# Adafruit_Feather_M0_Adalogger.net
KiCad netlist of a schematic drawn in EAGLE
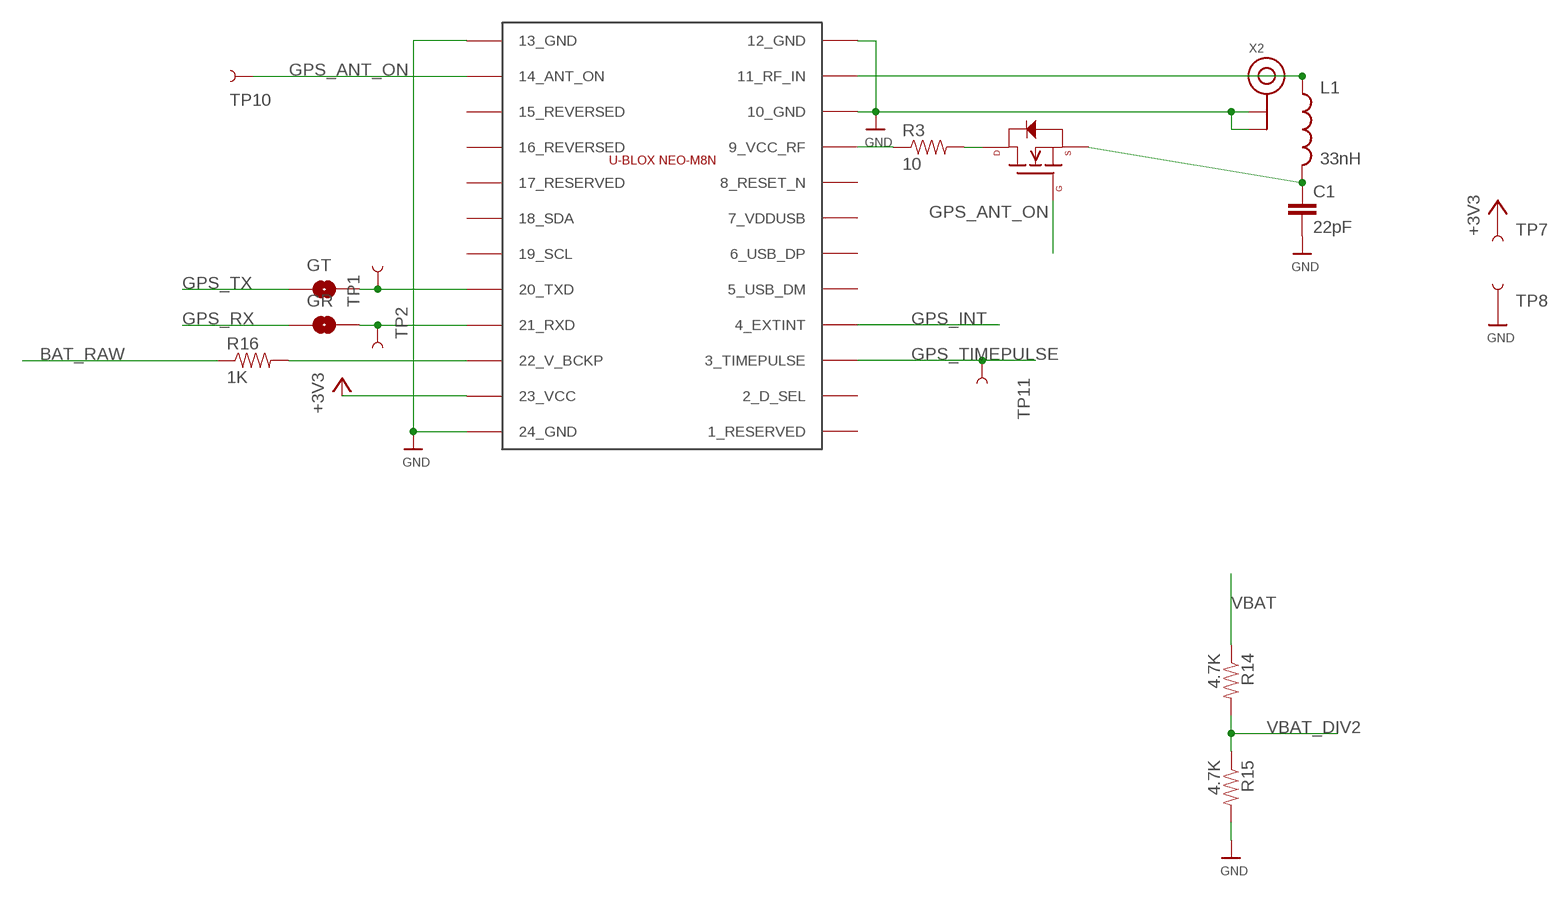
[diagram p0: schematic, sheet 1, part 1 of 2]
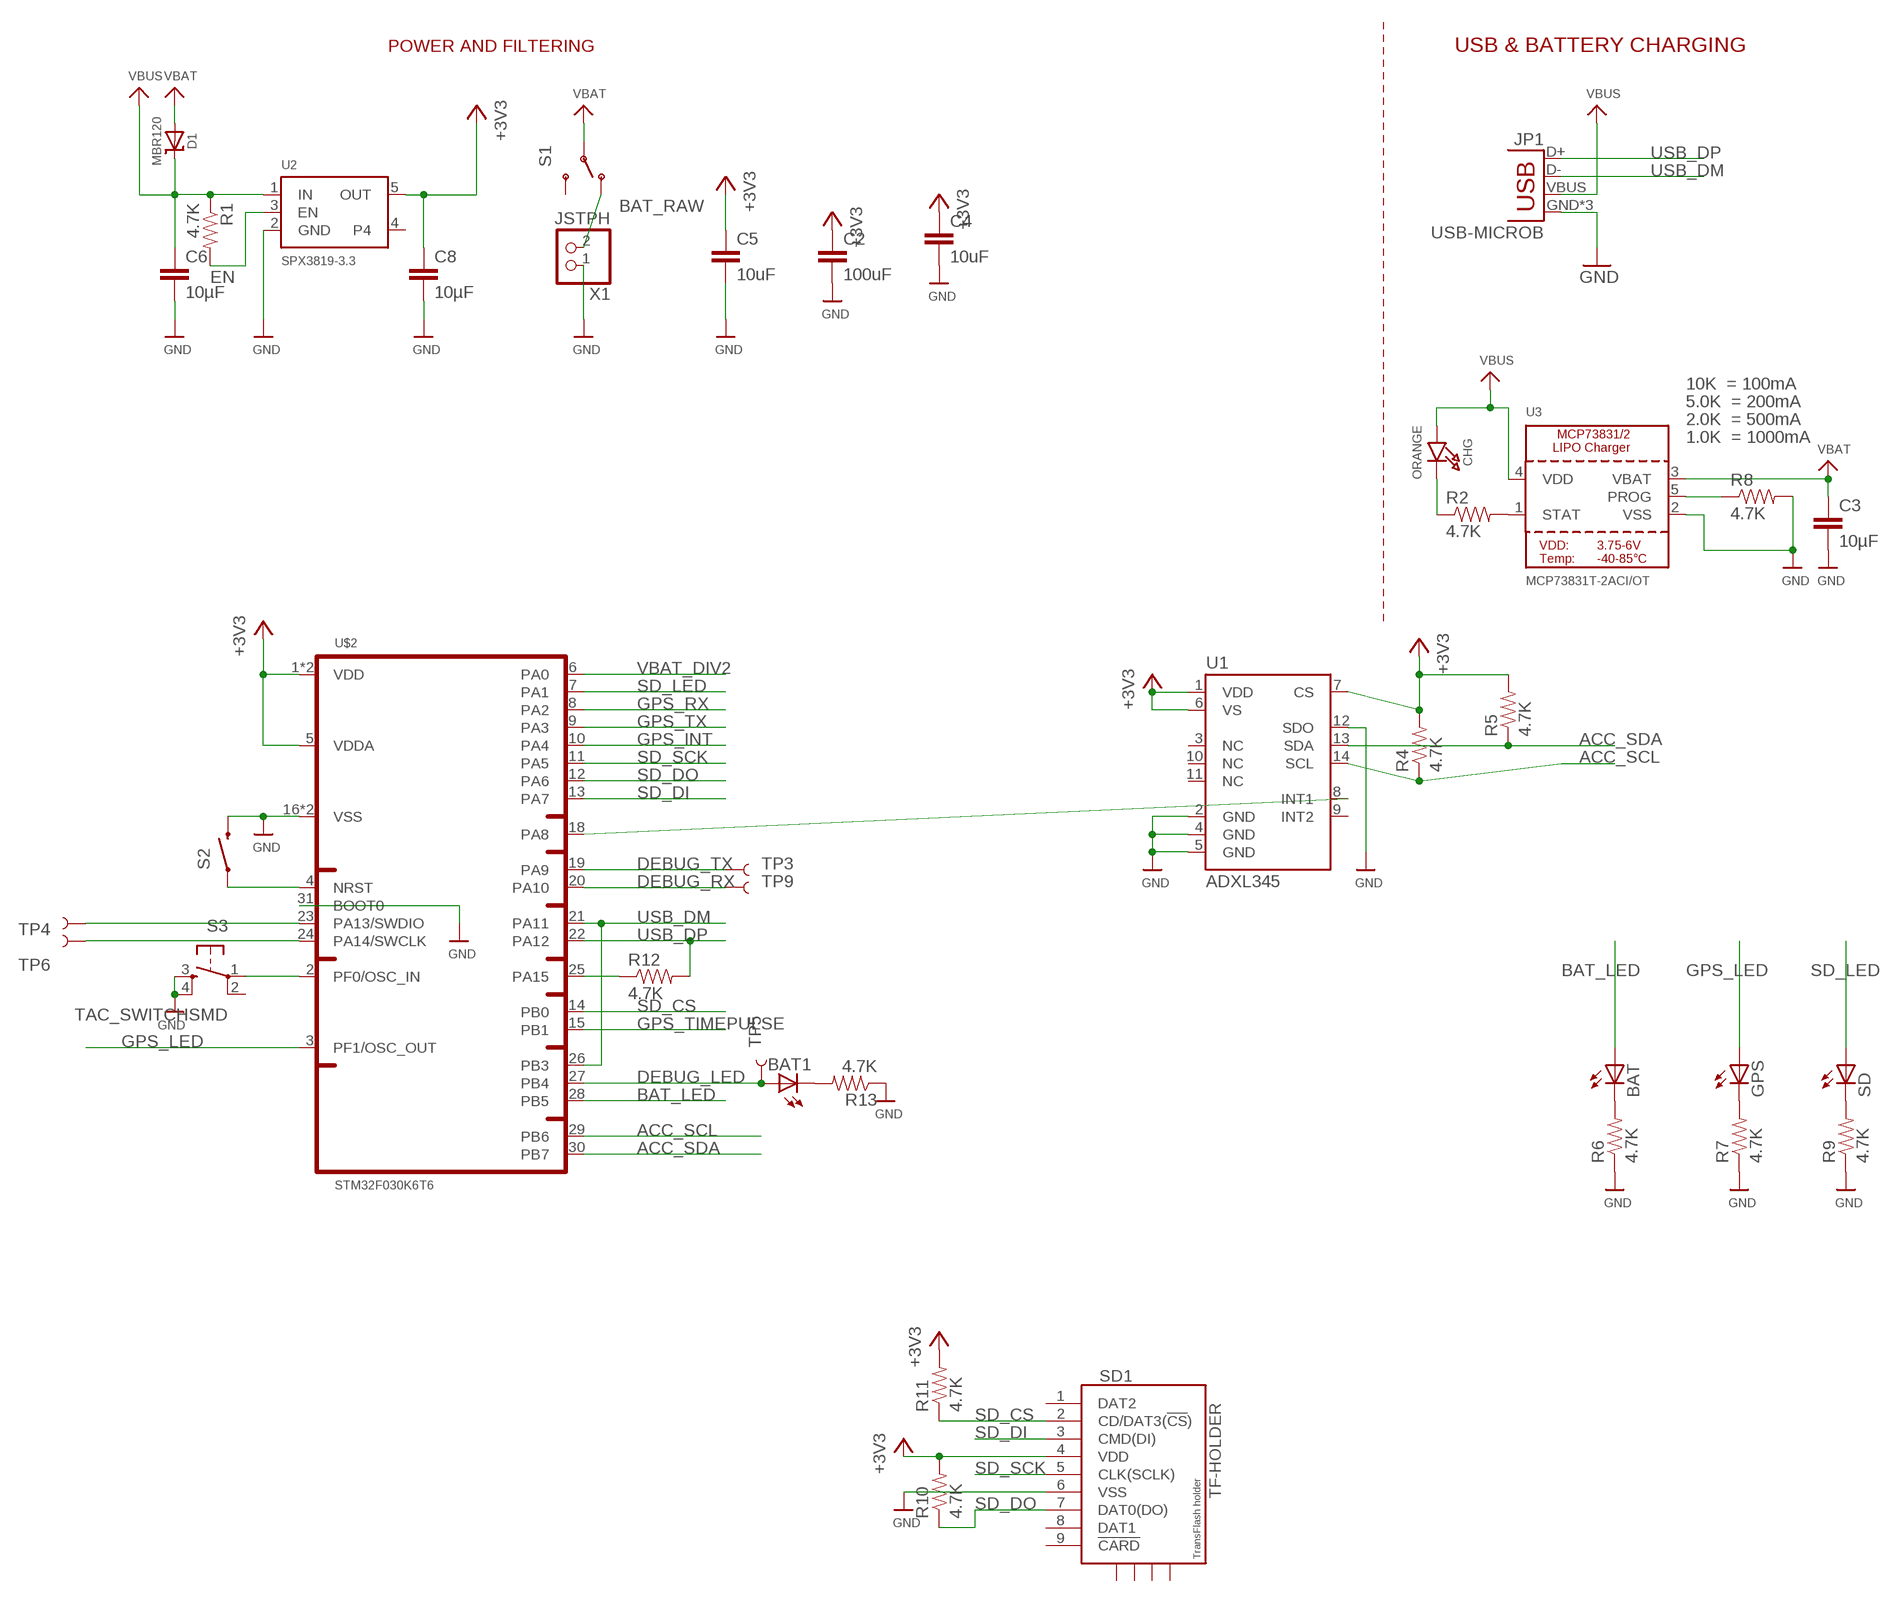
[diagram p1: schematic, sheet 1, part 2 of 2]

(export (version "E")
  (design (tool "Eeschema 10.0.6"))
  (components
    (comp (ref "BAT")
      (value "LEDCHIPLED_0805")
      (footprint "eagle-import:CHIPLED_0805")
      (libsource (lib "eagle-import") (part "LEDCHIPLED_0805"))
    )
    (comp (ref "BAT1")
      (value "LEDCHIPLED_0805")
      (footprint "eagle-import:CHIPLED_0805")
      (libsource (lib "eagle-import") (part "LEDCHIPLED_0805"))
    )
    (comp (ref "C1")
      (value "22pF")
      (footprint "eagle-import:0805")
      (libsource (lib "eagle-import") (part "CAP0805"))
    )
    (comp (ref "C2")
      (value "100uF")
      (footprint "eagle-import:1210")
      (libsource (lib "eagle-import") (part "100UF6.3V20%(1210)"))
    )
    (comp (ref "C3")
      (value "10µF")
      (footprint "eagle-import:0805")
      (libsource (lib "eagle-import") (part "CAP0805"))
    )
    (comp (ref "C4")
      (value "10uF")
      (footprint "eagle-import:0805")
      (libsource (lib "eagle-import") (part "CAP0805"))
    )
    (comp (ref "C5")
      (value "10uF")
      (footprint "eagle-import:0805")
      (libsource (lib "eagle-import") (part "CAP0805"))
    )
    (comp (ref "C6")
      (value "10µF")
      (footprint "eagle-import:0805")
      (libsource (lib "eagle-import") (part "CAP0805"))
    )
    (comp (ref "C8")
      (value "10µF")
      (footprint "eagle-import:0805")
      (libsource (lib "eagle-import") (part "CAP0805"))
    )
    (comp (ref "CHG")
      (value "ORANGE")
      (footprint "eagle-import:CHIPLED_0805_NOOUTLINE")
      (libsource (lib "eagle-import") (part "LED0805_NOOUTLINE"))
    )
    (comp (ref "D1")
      (value "MBR120")
      (footprint "eagle-import:SOD-123")
      (libsource (lib "eagle-import") (part "DIODE-SCHOTTKYSOD-123"))
    )
    (comp (ref "DEKU1")
      (value "UBLOX_NEO-M8N")
      (footprint "eagle-import:UBLOX_NEO-M8N")
      (libsource (lib "eagle-import") (part "UBLOX_NEO-M8N"))
    )
    (comp (ref "GPS")
      (value "LEDCHIPLED_0805")
      (footprint "eagle-import:CHIPLED_0805")
      (libsource (lib "eagle-import") (part "LEDCHIPLED_0805"))
    )
    (comp (ref "GR")
      (value "JUMPER-PAD-2-NO")
      (footprint "eagle-import:PAD-JUMPER-2-NO_NO_SILK")
      (libsource (lib "eagle-import") (part "JUMPER-PAD-2-NO"))
    )
    (comp (ref "GT")
      (value "JUMPER-PAD-2-NO")
      (footprint "eagle-import:PAD-JUMPER-2-NO_NO_SILK")
      (libsource (lib "eagle-import") (part "JUMPER-PAD-2-NO"))
    )
    (comp (ref "JP1")
      (value "USB-MICROB")
      (footprint "eagle-import:USB-MICROB")
      (libsource (lib "eagle-import") (part "USB-MICROB"))
    )
    (comp (ref "L1")
      (value "33nH")
      (footprint "eagle-import:0805")
      (libsource (lib "eagle-import") (part "INDUCTOR0805"))
    )
    (comp (ref "R1")
      (value "4.7K")
      (footprint "eagle-import:0805")
      (libsource (lib "eagle-import") (part "RESISTOR0805-RES"))
    )
    (comp (ref "R2")
      (value "4.7K")
      (footprint "eagle-import:0805")
      (libsource (lib "eagle-import") (part "RESISTOR0805-RES"))
    )
    (comp (ref "R3")
      (value "10")
      (footprint "eagle-import:0805")
      (libsource (lib "eagle-import") (part "RESISTOR0805-RES"))
    )
    (comp (ref "R4")
      (value "4.7K")
      (footprint "eagle-import:0805")
      (libsource (lib "eagle-import") (part "RESISTOR0805-RES"))
    )
    (comp (ref "R5")
      (value "4.7K")
      (footprint "eagle-import:0805")
      (libsource (lib "eagle-import") (part "RESISTOR0805-RES"))
    )
    (comp (ref "R6")
      (value "4.7K")
      (footprint "eagle-import:0805")
      (libsource (lib "eagle-import") (part "RESISTOR0805-RES"))
    )
    (comp (ref "R7")
      (value "4.7K")
      (footprint "eagle-import:0805")
      (libsource (lib "eagle-import") (part "RESISTOR0805-RES"))
    )
    (comp (ref "R8")
      (value "4.7K")
      (footprint "eagle-import:0805")
      (libsource (lib "eagle-import") (part "RESISTOR0805-RES"))
    )
    (comp (ref "R9")
      (value "4.7K")
      (footprint "eagle-import:0805")
      (libsource (lib "eagle-import") (part "RESISTOR0805-RES"))
    )
    (comp (ref "R10")
      (value "4.7K")
      (footprint "eagle-import:0805")
      (libsource (lib "eagle-import") (part "RESISTOR0805-RES"))
    )
    (comp (ref "R11")
      (value "4.7K")
      (footprint "eagle-import:0805")
      (libsource (lib "eagle-import") (part "RESISTOR0805-RES"))
    )
    (comp (ref "R12")
      (value "4.7K")
      (footprint "eagle-import:0805")
      (libsource (lib "eagle-import") (part "RESISTOR0805-RES"))
    )
    (comp (ref "R13")
      (value "4.7K")
      (footprint "eagle-import:0805")
      (libsource (lib "eagle-import") (part "RESISTOR0805-RES"))
    )
    (comp (ref "R14")
      (value "4.7K")
      (footprint "eagle-import:0805")
      (libsource (lib "eagle-import") (part "RESISTOR0805-RES"))
    )
    (comp (ref "R15")
      (value "4.7K")
      (footprint "eagle-import:0805")
      (libsource (lib "eagle-import") (part "RESISTOR0805-RES"))
    )
    (comp (ref "R16")
      (value "1K")
      (footprint "eagle-import:0805")
      (libsource (lib "eagle-import") (part "RESISTOR0805-RES"))
    )
    (comp (ref "S1")
      (value "SWITCH-SPDT-SMD-A")
      (footprint "eagle-import:SWITCH-SPST-SMD-A")
      (libsource (lib "eagle-import") (part "SWITCH-SPDT-SMD-A"))
    )
    (comp (ref "S2")
      (value "SWITCH-MOMENTARY-2TURTLE")
      (footprint "eagle-import:KMR2")
      (libsource (lib "eagle-import") (part "SWITCH-MOMENTARY-2TURTLE"))
    )
    (comp (ref "S3")
      (value "TAC_SWITCHSMD")
      (footprint "eagle-import:TACTILE-SWITCH-SMD")
      (libsource (lib "eagle-import") (part "TAC_SWITCHSMD"))
    )
    (comp (ref "SD")
      (value "LEDCHIPLED_0805")
      (footprint "eagle-import:CHIPLED_0805")
      (libsource (lib "eagle-import") (part "LEDCHIPLED_0805"))
    )
    (comp (ref "SD1")
      (value "TF-HOLDER")
      (footprint "eagle-import:TF-PULL")
      (libsource (lib "eagle-import") (part "TF-HOLDER"))
    )
    (comp (ref "TP1")
      (value "TEST-POINT3X5")
      (footprint "eagle-import:PAD.03X.05")
      (libsource (lib "eagle-import") (part "TEST-POINT3X5"))
    )
    (comp (ref "TP2")
      (value "TEST-POINT3X5")
      (footprint "eagle-import:PAD.03X.05")
      (libsource (lib "eagle-import") (part "TEST-POINT3X5"))
    )
    (comp (ref "TP3")
      (value "TEST-POINT3X5")
      (footprint "eagle-import:PAD.03X.05")
      (libsource (lib "eagle-import") (part "TEST-POINT3X5"))
    )
    (comp (ref "TP4")
      (value "TEST-POINT3X5")
      (footprint "eagle-import:PAD.03X.05")
      (libsource (lib "eagle-import") (part "TEST-POINT3X5"))
    )
    (comp (ref "TP5")
      (value "TEST-POINT3X5")
      (footprint "eagle-import:PAD.03X.05")
      (libsource (lib "eagle-import") (part "TEST-POINT3X5"))
    )
    (comp (ref "TP6")
      (value "TEST-POINT3X5")
      (footprint "eagle-import:PAD.03X.05")
      (libsource (lib "eagle-import") (part "TEST-POINT3X5"))
    )
    (comp (ref "TP7")
      (value "TEST-POINT3X5")
      (footprint "eagle-import:PAD.03X.05")
      (libsource (lib "eagle-import") (part "TEST-POINT3X5"))
    )
    (comp (ref "TP8")
      (value "TEST-POINT3X5")
      (footprint "eagle-import:PAD.03X.05")
      (libsource (lib "eagle-import") (part "TEST-POINT3X5"))
    )
    (comp (ref "TP9")
      (value "TEST-POINT3X5")
      (footprint "eagle-import:PAD.03X.05")
      (libsource (lib "eagle-import") (part "TEST-POINT3X5"))
    )
    (comp (ref "TP10")
      (value "TEST-POINT3X5")
      (footprint "eagle-import:PAD.03X.05")
      (libsource (lib "eagle-import") (part "TEST-POINT3X5"))
    )
    (comp (ref "TP11")
      (value "TEST-POINT3X5")
      (footprint "eagle-import:PAD.03X.05")
      (libsource (lib "eagle-import") (part "TEST-POINT3X5"))
    )
    (comp (ref "U$2")
      (value "STM32F030K6T6")
      (footprint "eagle-import:TQFP32-08")
      (libsource (lib "eagle-import") (part "STM32F030K6T6"))
    )
    (comp (ref "U$24")
      (value "N-CHANNEL-MOSFET-BSS138")
      (footprint "eagle-import:SOT23-3")
      (libsource (lib "eagle-import") (part "N-CHANNEL-MOSFET-BSS138"))
    )
    (comp (ref "U1")
      (value "ADXL345")
      (footprint "eagle-import:LGA14")
      (libsource (lib "eagle-import") (part "ADXL345"))
    )
    (comp (ref "U2")
      (value "SPX3819-3.3")
      (footprint "eagle-import:SOT23-5")
      (libsource (lib "eagle-import") (part "VREG_SOT23-5"))
    )
    (comp (ref "U3")
      (value "MCP73831T-2ACI/OT")
      (footprint "eagle-import:SOT23-5")
      (libsource (lib "eagle-import") (part "MCP73831/2"))
    )
    (comp (ref "X1")
      (value "JSTPH")
      (footprint "eagle-import:JSTPH2")
      (libsource (lib "eagle-import") (part "CON_JST_PH_2PIN"))
    )
    (comp (ref "X2")
      (value "ANTENNA_U.FL")
      (footprint "eagle-import:U.FL")
      (libsource (lib "eagle-import") (part "ANTENNA_U.FL"))
    )
  )
  (nets
    (net (code "1") (name "+3V3") (class "Default")
      (node (ref "C2") (pin "1") (pinfunction "1_1") (pintype "passive"))
      (node (ref "C4") (pin "1") (pinfunction "1_1") (pintype "passive"))
      (node (ref "C5") (pin "1") (pinfunction "1_1") (pintype "passive"))
      (node (ref "C8") (pin "1") (pinfunction "1_1") (pintype "passive"))
      (node (ref "DEKU1") (pin "23_VCC") (pinfunction "23_VCC_23_VCC") (pintype "bidirectional"))
      (node (ref "R10") (pin "2") (pinfunction "2_2") (pintype "passive"))
      (node (ref "R11") (pin "2") (pinfunction "2_2") (pintype "passive"))
      (node (ref "R4") (pin "2") (pinfunction "2_2") (pintype "passive"))
      (node (ref "R5") (pin "2") (pinfunction "2_2") (pintype "passive"))
      (node (ref "SD1") (pin "4") (pinfunction "VDD_4") (pintype "power_in"))
      (node (ref "TP7") (pin "P$1") (pinfunction "1_P$1") (pintype "bidirectional"))
      (node (ref "U$2") (pin "1") (pinfunction "VDD_1") (pintype "bidirectional"))
      (node (ref "U$2") (pin "17") (pinfunction "VDD_17") (pintype "bidirectional"))
      (node (ref "U$2") (pin "5") (pinfunction "VDDA_5") (pintype "bidirectional"))
      (node (ref "U1") (pin "1") (pinfunction "VDD_1") (pintype "bidirectional"))
      (node (ref "U1") (pin "6") (pinfunction "VS_6") (pintype "bidirectional"))
      (node (ref "U1") (pin "7") (pinfunction "CS_7") (pintype "bidirectional"))
      (node (ref "U2") (pin "5") (pinfunction "OUT_5") (pintype "power_in"))
    )
    (net (code "2") (name "/ACC_SCL") (class "Default")
      (node (ref "R4") (pin "1") (pinfunction "1_1") (pintype "passive"))
      (node (ref "U$2") (pin "29") (pinfunction "PB6_29") (pintype "bidirectional"))
      (node (ref "U1") (pin "14") (pinfunction "SCL_14") (pintype "bidirectional"))
    )
    (net (code "3") (name "/ACC_SDA") (class "Default")
      (node (ref "R5") (pin "1") (pinfunction "1_1") (pintype "passive"))
      (node (ref "U$2") (pin "30") (pinfunction "PB7_30") (pintype "bidirectional"))
      (node (ref "U1") (pin "13") (pinfunction "SDA_13") (pintype "bidirectional"))
    )
    (net (code "4") (name "/BAT_LED") (class "Default")
      (node (ref "BAT") (pin "A") (pinfunction "A_A") (pintype "passive"))
      (node (ref "U$2") (pin "28") (pinfunction "PB5_28") (pintype "bidirectional"))
    )
    (net (code "5") (name "/BAT_RAW") (class "Default")
      (node (ref "R16") (pin "1") (pinfunction "1_1") (pintype "passive"))
      (node (ref "S1") (pin "1") (pinfunction "O_1") (pintype "passive"))
      (node (ref "X1") (pin "2") (pinfunction "2_2") (pintype "passive"))
    )
    (net (code "6") (name "/DEBUG_LED") (class "Default")
      (node (ref "BAT1") (pin "A") (pinfunction "A_A") (pintype "passive"))
      (node (ref "TP5") (pin "P$1") (pinfunction "1_P$1") (pintype "bidirectional"))
      (node (ref "U$2") (pin "27") (pinfunction "PB4_27") (pintype "bidirectional"))
    )
    (net (code "7") (name "/DEBUG_RX") (class "Default")
      (node (ref "TP9") (pin "P$1") (pinfunction "1_P$1") (pintype "bidirectional"))
      (node (ref "U$2") (pin "20") (pinfunction "PA10_20") (pintype "bidirectional"))
    )
    (net (code "8") (name "/DEBUG_TX") (class "Default")
      (node (ref "TP3") (pin "P$1") (pinfunction "1_P$1") (pintype "bidirectional"))
      (node (ref "U$2") (pin "19") (pinfunction "PA9_19") (pintype "bidirectional"))
    )
    (net (code "9") (name "/EN") (class "Default")
      (node (ref "R1") (pin "2") (pinfunction "2_2") (pintype "passive"))
      (node (ref "U2") (pin "3") (pinfunction "EN_3") (pintype "input"))
    )
    (net (code "10") (name "/GPS_ANT_ON") (class "Default")
      (node (ref "DEKU1") (pin "14_ANT_ON") (pinfunction "14_ANT_ON_14_ANT_ON") (pintype "bidirectional"))
      (node (ref "TP10") (pin "P$1") (pinfunction "1_P$1") (pintype "bidirectional"))
      (node (ref "U$24") (pin "1") (pinfunction "G_1") (pintype "passive"))
    )
    (net (code "11") (name "/GPS_INT") (class "Default")
      (node (ref "DEKU1") (pin "4_EXTINT") (pinfunction "4_EXTINT_4_EXTINT") (pintype "bidirectional"))
      (node (ref "U$2") (pin "10") (pinfunction "PA4_10") (pintype "bidirectional"))
    )
    (net (code "12") (name "/GPS_LED") (class "Default")
      (node (ref "GPS") (pin "A") (pinfunction "A_A") (pintype "passive"))
      (node (ref "U$2") (pin "3") (pinfunction "PF1/OSC_OUT_3") (pintype "bidirectional"))
    )
    (net (code "13") (name "/GPS_RX") (class "Default")
      (node (ref "GR") (pin "1") (pinfunction "1_1") (pintype "passive"))
      (node (ref "U$2") (pin "8") (pinfunction "PA2_8") (pintype "bidirectional"))
    )
    (net (code "14") (name "/GPS_TIMEPULSE") (class "Default")
      (node (ref "DEKU1") (pin "3_TIMEPULSE") (pinfunction "3_TIMEPULSE_3_TIMEPULSE") (pintype "bidirectional"))
      (node (ref "TP11") (pin "P$1") (pinfunction "1_P$1") (pintype "bidirectional"))
      (node (ref "U$2") (pin "15") (pinfunction "PB1_15") (pintype "bidirectional"))
    )
    (net (code "15") (name "/GPS_TX") (class "Default")
      (node (ref "GT") (pin "1") (pinfunction "1_1") (pintype "passive"))
      (node (ref "U$2") (pin "9") (pinfunction "PA3_9") (pintype "bidirectional"))
    )
    (net (code "16") (name "/SD_CS") (class "Default")
      (node (ref "R11") (pin "1") (pinfunction "1_1") (pintype "passive"))
      (node (ref "SD1") (pin "2") (pinfunction "CD/DAT3(~{CS})_2") (pintype "bidirectional"))
      (node (ref "U$2") (pin "14") (pinfunction "PB0_14") (pintype "bidirectional"))
    )
    (net (code "17") (name "/SD_DI") (class "Default")
      (node (ref "SD1") (pin "3") (pinfunction "CMD(DI)_3") (pintype "bidirectional"))
      (node (ref "U$2") (pin "13") (pinfunction "PA7_13") (pintype "bidirectional"))
    )
    (net (code "18") (name "/SD_DO") (class "Default")
      (node (ref "R10") (pin "1") (pinfunction "1_1") (pintype "passive"))
      (node (ref "SD1") (pin "7") (pinfunction "DAT0(DO)_7") (pintype "bidirectional"))
      (node (ref "U$2") (pin "12") (pinfunction "PA6_12") (pintype "bidirectional"))
    )
    (net (code "19") (name "/SD_LED") (class "Default")
      (node (ref "SD") (pin "A") (pinfunction "A_A") (pintype "passive"))
      (node (ref "U$2") (pin "7") (pinfunction "PA1_7") (pintype "bidirectional"))
    )
    (net (code "20") (name "/SD_SCK") (class "Default")
      (node (ref "SD1") (pin "5") (pinfunction "CLK(SCLK)_5") (pintype "input"))
      (node (ref "U$2") (pin "11") (pinfunction "PA5_11") (pintype "bidirectional"))
    )
    (net (code "21") (name "/USB_DM") (class "Default")
      (node (ref "JP1") (pin "D-") (pinfunction "D-_D-") (pintype "bidirectional"))
      (node (ref "U$2") (pin "21") (pinfunction "PA11_21") (pintype "bidirectional"))
      (node (ref "U$2") (pin "26") (pinfunction "PB3_26") (pintype "bidirectional"))
    )
    (net (code "22") (name "/USB_DP") (class "Default")
      (node (ref "JP1") (pin "D+") (pinfunction "D+_D+") (pintype "bidirectional"))
      (node (ref "R12") (pin "2") (pinfunction "2_2") (pintype "passive"))
      (node (ref "U$2") (pin "22") (pinfunction "PA12_22") (pintype "bidirectional"))
    )
    (net (code "23") (name "/VBAT_DIV2") (class "Default")
      (node (ref "R14") (pin "2") (pinfunction "2_2") (pintype "passive"))
      (node (ref "R15") (pin "1") (pinfunction "1_1") (pintype "passive"))
      (node (ref "U$2") (pin "6") (pinfunction "PA0_6") (pintype "bidirectional"))
    )
    (net (code "24") (name "GND") (class "Default")
      (node (ref "C1") (pin "2") (pinfunction "2_2") (pintype "passive"))
      (node (ref "C2") (pin "2") (pinfunction "2_2") (pintype "passive"))
      (node (ref "C3") (pin "2") (pinfunction "2_2") (pintype "passive"))
      (node (ref "C4") (pin "2") (pinfunction "2_2") (pintype "passive"))
      (node (ref "C5") (pin "2") (pinfunction "2_2") (pintype "passive"))
      (node (ref "C6") (pin "2") (pinfunction "2_2") (pintype "passive"))
      (node (ref "C8") (pin "2") (pinfunction "2_2") (pintype "passive"))
      (node (ref "DEKU1") (pin "10_GND") (pinfunction "10_GND_10_GND") (pintype "bidirectional"))
      (node (ref "DEKU1") (pin "12_GND") (pinfunction "12_GND_12_GND") (pintype "bidirectional"))
      (node (ref "DEKU1") (pin "13_GND") (pinfunction "13_GND_13_GND") (pintype "bidirectional"))
      (node (ref "DEKU1") (pin "24_GND") (pinfunction "24_GND_24_GND") (pintype "bidirectional"))
      (node (ref "JP1") (pin "GND") (pinfunction "GND_GND") (pintype "bidirectional"))
      (node (ref "JP1") (pin "MT1") (pinfunction "GND_MT1") (pintype "bidirectional"))
      (node (ref "JP1") (pin "MT2") (pinfunction "GND_MT2") (pintype "bidirectional"))
      (node (ref "R13") (pin "1") (pinfunction "1_1") (pintype "passive"))
      (node (ref "R15") (pin "2") (pinfunction "2_2") (pintype "passive"))
      (node (ref "R6") (pin "1") (pinfunction "1_1") (pintype "passive"))
      (node (ref "R7") (pin "1") (pinfunction "1_1") (pintype "passive"))
      (node (ref "R8") (pin "2") (pinfunction "2_2") (pintype "passive"))
      (node (ref "R9") (pin "1") (pinfunction "1_1") (pintype "passive"))
      (node (ref "S2") (pin "3") (pinfunction "2_3") (pintype "passive"))
      (node (ref "S3") (pin "3") (pinfunction "3_3") (pintype "passive"))
      (node (ref "S3") (pin "4") (pinfunction "4_4") (pintype "passive"))
      (node (ref "SD1") (pin "6") (pinfunction "VSS_6") (pintype "power_in"))
      (node (ref "TP8") (pin "P$1") (pinfunction "1_P$1") (pintype "bidirectional"))
      (node (ref "U$2") (pin "16") (pinfunction "VSS_16") (pintype "bidirectional"))
      (node (ref "U$2") (pin "31") (pinfunction "BOOT0_31") (pintype "bidirectional"))
      (node (ref "U$2") (pin "32") (pinfunction "VSS_32") (pintype "bidirectional"))
      (node (ref "U1") (pin "12") (pinfunction "SDO_12") (pintype "bidirectional"))
      (node (ref "U1") (pin "2") (pinfunction "GND_2") (pintype "bidirectional"))
      (node (ref "U1") (pin "4") (pinfunction "GND_4") (pintype "bidirectional"))
      (node (ref "U1") (pin "5") (pinfunction "GND_5") (pintype "bidirectional"))
      (node (ref "U2") (pin "2") (pinfunction "GND_2") (pintype "power_in"))
      (node (ref "U3") (pin "2") (pinfunction "VSS_2") (pintype "power_in"))
      (node (ref "X1") (pin "1") (pinfunction "1_1") (pintype "passive"))
      (node (ref "X2") (pin "1") (pinfunction "GND_1") (pintype "passive"))
      (node (ref "X2") (pin "2") (pinfunction "GND_2") (pintype "passive"))
    )
    (net (code "25") (name "Net-(BAT-PadC)") (class "Default")
      (node (ref "BAT") (pin "C") (pinfunction "C_C") (pintype "passive"))
      (node (ref "R6") (pin "2") (pinfunction "2_2") (pintype "passive"))
    )
    (net (code "26") (name "Net-(BAT1-PadC)") (class "Default")
      (node (ref "BAT1") (pin "C") (pinfunction "C_C") (pintype "passive"))
      (node (ref "R13") (pin "2") (pinfunction "2_2") (pintype "passive"))
    )
    (net (code "27") (name "Net-(CHG-PadC)") (class "Default")
      (node (ref "CHG") (pin "C") (pinfunction "C_C") (pintype "passive"))
      (node (ref "R2") (pin "1") (pinfunction "1_1") (pintype "passive"))
    )
    (net (code "28") (name "Net-(DEKU1-Pad9_VCC_RF)") (class "Default")
      (node (ref "DEKU1") (pin "9_VCC_RF") (pinfunction "9_VCC_RF_9_VCC_RF") (pintype "bidirectional"))
      (node (ref "R3") (pin "1") (pinfunction "1_1") (pintype "passive"))
    )
    (net (code "29") (name "Net-(DEKU1-Pad22_V_BCKP)") (class "Default")
      (node (ref "DEKU1") (pin "22_V_BCKP") (pinfunction "22_V_BCKP_22_V_BCKP") (pintype "bidirectional"))
      (node (ref "R16") (pin "2") (pinfunction "2_2") (pintype "passive"))
    )
    (net (code "30") (name "Net-(GPS-PadC)") (class "Default")
      (node (ref "GPS") (pin "C") (pinfunction "C_C") (pintype "passive"))
      (node (ref "R7") (pin "2") (pinfunction "2_2") (pintype "passive"))
    )
    (net (code "31") (name "Net-(R9-Pad2)") (class "Default")
      (node (ref "R9") (pin "2") (pinfunction "2_2") (pintype "passive"))
      (node (ref "SD") (pin "C") (pinfunction "C_C") (pintype "passive"))
    )
    (net (code "32") (name "Net-(TP1-1)") (class "Default")
      (node (ref "DEKU1") (pin "20_TXD") (pinfunction "20_TXD_20_TXD") (pintype "bidirectional"))
      (node (ref "GT") (pin "2") (pinfunction "2_2") (pintype "passive"))
      (node (ref "TP1") (pin "P$1") (pinfunction "1_P$1") (pintype "bidirectional"))
    )
    (net (code "33") (name "Net-(TP2-1)") (class "Default")
      (node (ref "DEKU1") (pin "21_RXD") (pinfunction "21_RXD_21_RXD") (pintype "bidirectional"))
      (node (ref "GR") (pin "2") (pinfunction "2_2") (pintype "passive"))
      (node (ref "TP2") (pin "P$1") (pinfunction "1_P$1") (pintype "bidirectional"))
    )
    (net (code "34") (name "Net-(TP4-1)") (class "Default")
      (node (ref "TP4") (pin "P$1") (pinfunction "1_P$1") (pintype "bidirectional"))
      (node (ref "U$2") (pin "23") (pinfunction "PA13/SWDIO_23") (pintype "bidirectional"))
    )
    (net (code "35") (name "Net-(TP6-1)") (class "Default")
      (node (ref "TP6") (pin "P$1") (pinfunction "1_P$1") (pintype "bidirectional"))
      (node (ref "U$2") (pin "24") (pinfunction "PA14/SWCLK_24") (pintype "bidirectional"))
    )
    (net (code "36") (name "Net-(U$2-NRST)") (class "Default")
      (node (ref "S2") (pin "1") (pinfunction "1_1") (pintype "passive"))
      (node (ref "U$2") (pin "4") (pinfunction "NRST_4") (pintype "bidirectional"))
    )
    (net (code "37") (name "Net-(U$2-PA8)") (class "Default")
      (node (ref "U$2") (pin "18") (pinfunction "PA8_18") (pintype "bidirectional"))
      (node (ref "U1") (pin "8") (pinfunction "INT1_8") (pintype "bidirectional"))
    )
    (net (code "38") (name "Net-(U$2-PA15)") (class "Default")
      (node (ref "R12") (pin "1") (pinfunction "1_1") (pintype "passive"))
      (node (ref "U$2") (pin "25") (pinfunction "PA15_25") (pintype "bidirectional"))
    )
    (net (code "39") (name "Net-(U$2-PF0{slash}OSC_IN)") (class "Default")
      (node (ref "S3") (pin "1") (pinfunction "1_1") (pintype "passive"))
      (node (ref "U$2") (pin "2") (pinfunction "PF0/OSC_IN_2") (pintype "bidirectional"))
    )
    (net (code "40") (name "Net-(U$24-D)") (class "Default")
      (node (ref "R3") (pin "2") (pinfunction "2_2") (pintype "passive"))
      (node (ref "U$24") (pin "3") (pinfunction "D_3") (pintype "passive"))
    )
    (net (code "41") (name "Net-(U$24-S)") (class "Default")
      (node (ref "C1") (pin "1") (pinfunction "1_1") (pintype "passive"))
      (node (ref "L1") (pin "2") (pinfunction "2_2") (pintype "passive"))
      (node (ref "U$24") (pin "2") (pinfunction "S_2") (pintype "passive"))
    )
    (net (code "42") (name "Net-(U3-PROG)") (class "Default")
      (node (ref "R8") (pin "1") (pinfunction "1_1") (pintype "passive"))
      (node (ref "U3") (pin "5") (pinfunction "PROG_5") (pintype "input"))
    )
    (net (code "43") (name "Net-(U3-STAT)") (class "Default")
      (node (ref "R2") (pin "2") (pinfunction "2_2") (pintype "passive"))
      (node (ref "U3") (pin "1") (pinfunction "STAT_1") (pintype "output"))
    )
    (net (code "44") (name "Net-(X2-SIGNAL)") (class "Default")
      (node (ref "DEKU1") (pin "11_RF_IN") (pinfunction "11_RF_IN_11_RF_IN") (pintype "bidirectional"))
      (node (ref "L1") (pin "1") (pinfunction "1_1") (pintype "passive"))
      (node (ref "X2") (pin "3") (pinfunction "SIGNAL_3") (pintype "passive"))
    )
    (net (code "45") (name "VBAT") (class "Default")
      (node (ref "C3") (pin "1") (pinfunction "1_1") (pintype "passive"))
      (node (ref "D1") (pin "A") (pinfunction "A_A") (pintype "passive"))
      (node (ref "R14") (pin "1") (pinfunction "1_1") (pintype "passive"))
      (node (ref "S1") (pin "2") (pinfunction "P_2") (pintype "passive"))
      (node (ref "U3") (pin "3") (pinfunction "VBAT_3") (pintype "power_in"))
    )
    (net (code "46") (name "VBUS") (class "Default")
      (node (ref "C6") (pin "1") (pinfunction "1_1") (pintype "passive"))
      (node (ref "CHG") (pin "A") (pinfunction "A_A") (pintype "passive"))
      (node (ref "D1") (pin "C") (pinfunction "C_C") (pintype "passive"))
      (node (ref "JP1") (pin "VBUS") (pinfunction "VBUS_VBUS") (pintype "bidirectional"))
      (node (ref "R1") (pin "1") (pinfunction "1_1") (pintype "passive"))
      (node (ref "U2") (pin "1") (pinfunction "IN_1") (pintype "power_in"))
      (node (ref "U3") (pin "4") (pinfunction "VDD_4") (pintype "power_in"))
    )
    (net (code "47") (name "unconnected-(DEKU1-Pad1_RESERVED)") (class "Default")
      (node (ref "DEKU1") (pin "1_RESERVED") (pinfunction "1_RESERVED_1_RESERVED") (pintype "bidirectional"))
    )
    (net (code "48") (name "unconnected-(DEKU1-Pad2_D_SEL)") (class "Default")
      (node (ref "DEKU1") (pin "2_D_SEL") (pinfunction "2_D_SEL_2_D_SEL") (pintype "bidirectional"))
    )
    (net (code "49") (name "unconnected-(DEKU1-Pad5_USB_DM)") (class "Default")
      (node (ref "DEKU1") (pin "5_USB_DM") (pinfunction "5_USB_DM_5_USB_DM") (pintype "bidirectional"))
    )
    (net (code "50") (name "unconnected-(DEKU1-Pad6_USB_DP)") (class "Default")
      (node (ref "DEKU1") (pin "6_USB_DP") (pinfunction "6_USB_DP_6_USB_DP") (pintype "bidirectional"))
    )
    (net (code "51") (name "unconnected-(DEKU1-Pad7_VDDUSB)") (class "Default")
      (node (ref "DEKU1") (pin "7_VDDUSB") (pinfunction "7_VDDUSB_7_VDDUSB") (pintype "bidirectional"))
    )
    (net (code "52") (name "unconnected-(DEKU1-Pad8_RESET_N)") (class "Default")
      (node (ref "DEKU1") (pin "8_RESET_N") (pinfunction "8_RESET_N_8_RESET_N") (pintype "bidirectional"))
    )
    (net (code "53") (name "unconnected-(DEKU1-Pad15_REVERSED)") (class "Default")
      (node (ref "DEKU1") (pin "15_REVERSED") (pinfunction "15_REVERSED_15_REVERSED") (pintype "bidirectional"))
    )
    (net (code "54") (name "unconnected-(DEKU1-Pad16_REVERSED)") (class "Default")
      (node (ref "DEKU1") (pin "16_REVERSED") (pinfunction "16_REVERSED_16_REVERSED") (pintype "bidirectional"))
    )
    (net (code "55") (name "unconnected-(DEKU1-Pad17_RESERVED)") (class "Default")
      (node (ref "DEKU1") (pin "17_RESERVED") (pinfunction "17_RESERVED_17_RESERVED") (pintype "bidirectional"))
    )
    (net (code "56") (name "unconnected-(DEKU1-Pad18_SDA)") (class "Default")
      (node (ref "DEKU1") (pin "18_SDA") (pinfunction "18_SDA_18_SDA") (pintype "bidirectional"))
    )
    (net (code "57") (name "unconnected-(DEKU1-Pad19_SCL)") (class "Default")
      (node (ref "DEKU1") (pin "19_SCL") (pinfunction "19_SCL_19_SCL") (pintype "bidirectional"))
    )
    (net (code "58") (name "unconnected-(S1-S-Pad3)") (class "Default")
      (node (ref "S1") (pin "3") (pinfunction "S_3") (pintype "passive"))
    )
    (net (code "59") (name "unconnected-(S3-Pad2)") (class "Default")
      (node (ref "S3") (pin "2") (pinfunction "2_2") (pintype "passive"))
    )
    (net (code "60") (name "unconnected-(SD1-DAT1-Pad8)") (class "Default")
      (node (ref "SD1") (pin "8") (pinfunction "DAT1_8") (pintype "bidirectional"))
    )
    (net (code "61") (name "unconnected-(SD1-DAT2-Pad1)") (class "Default")
      (node (ref "SD1") (pin "1") (pinfunction "DAT2_1") (pintype "bidirectional"))
    )
    (net (code "62") (name "unconnected-(SD1-PadS1)") (class "Default")
      (node (ref "SD1") (pin "S1") (pinfunction "S1_S1") (pintype "passive"))
    )
    (net (code "63") (name "unconnected-(SD1-PadS2)") (class "Default")
      (node (ref "SD1") (pin "S2") (pinfunction "S2_S2") (pintype "passive"))
    )
    (net (code "64") (name "unconnected-(SD1-PadS3)") (class "Default")
      (node (ref "SD1") (pin "S3") (pinfunction "S3_S3") (pintype "passive"))
    )
    (net (code "65") (name "unconnected-(SD1-PadS4)") (class "Default")
      (node (ref "SD1") (pin "S4") (pinfunction "S4_S4") (pintype "passive"))
    )
    (net (code "66") (name "unconnected-(SD1-~{CARD}-Pad9)") (class "Default")
      (node (ref "SD1") (pin "9") (pinfunction "~{CARD}_9") (pintype "passive"))
    )
    (net (code "67") (name "unconnected-(U1-INT2-Pad9)") (class "Default")
      (node (ref "U1") (pin "9") (pinfunction "INT2_9") (pintype "bidirectional"))
    )
    (net (code "68") (name "unconnected-(U1-NC-Pad3)") (class "Default")
      (node (ref "U1") (pin "3") (pinfunction "NC_3") (pintype "bidirectional"))
    )
    (net (code "69") (name "unconnected-(U1-NC-Pad10)") (class "Default")
      (node (ref "U1") (pin "10") (pinfunction "NC_10") (pintype "bidirectional"))
    )
    (net (code "70") (name "unconnected-(U1-NC-Pad11)") (class "Default")
      (node (ref "U1") (pin "11") (pinfunction "NC_11") (pintype "bidirectional"))
    )
    (net (code "71") (name "unconnected-(U2-P4-Pad4)") (class "Default")
      (node (ref "U2") (pin "4") (pinfunction "P4_4") (pintype "bidirectional"))
    )
  )
)
